# aquatime.net
KiCad netlist of a schematic drawn in EAGLE
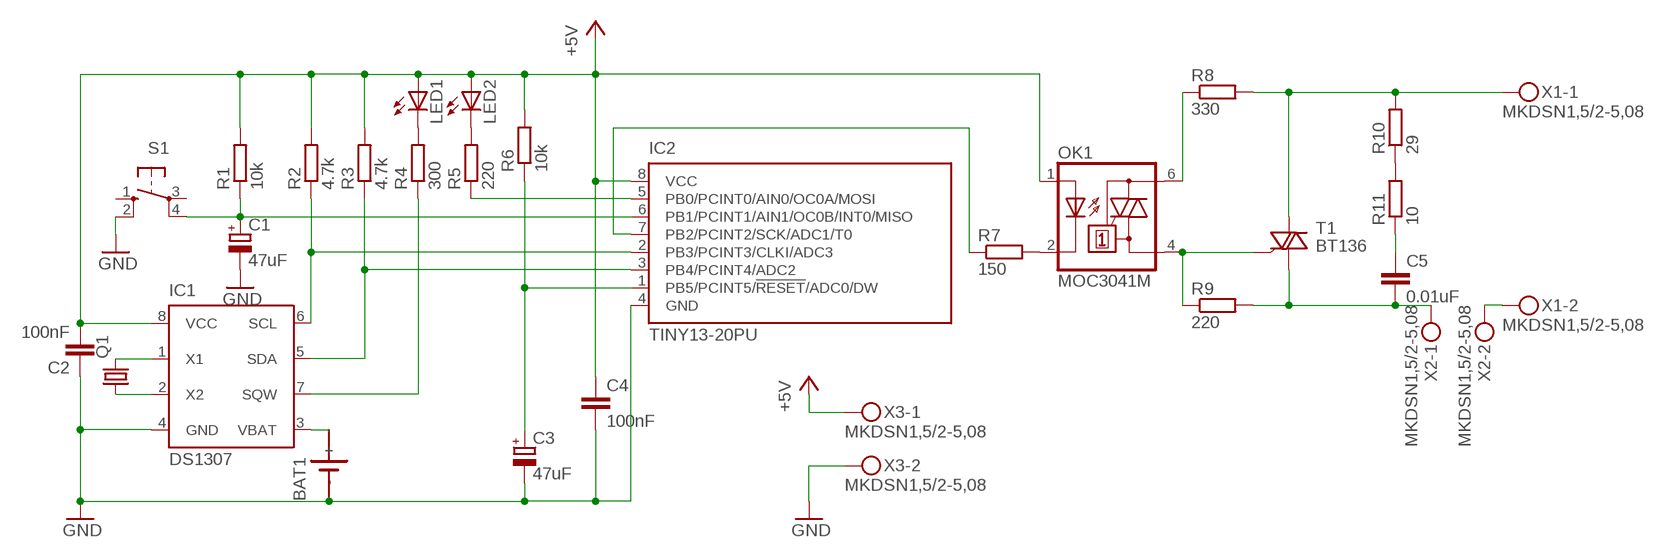
[diagram p0: schematic, sheet 1]

(export (version "E")
  (design (tool "Eeschema 10.0.6"))
  (components
    (comp (ref "BAT1")
      (value "SN2032")
      (footprint "eagle-import:SN2032")
      (libsource (lib "eagle-import") (part "SN2032"))
    )
    (comp (ref "C1")
      (value "47uF")
      (footprint "eagle-import:E2,5-6")
      (libsource (lib "eagle-import") (part "CPOL-EUE2.5-6"))
    )
    (comp (ref "C2")
      (value "100nF")
      (footprint "eagle-import:C102-064X133")
      (libsource (lib "eagle-import") (part "C-EU102-064X133"))
    )
    (comp (ref "C3")
      (value "47uF")
      (footprint "eagle-import:E2,5-6")
      (libsource (lib "eagle-import") (part "CPOL-EUE2.5-6"))
    )
    (comp (ref "C4")
      (value "100nF")
      (footprint "eagle-import:C102-064X133")
      (libsource (lib "eagle-import") (part "C-EU102-064X133"))
    )
    (comp (ref "C5")
      (value "0.01uF")
      (footprint "eagle-import:C102-064X133")
      (libsource (lib "eagle-import") (part "C-EU102-064X133"))
    )
    (comp (ref "IC1")
      (value "DS1307")
      (footprint "eagle-import:DIL08")
      (libsource (lib "eagle-import") (part "DS1307"))
    )
    (comp (ref "IC2")
      (value "TINY13-20PU")
      (footprint "eagle-import:DIL08")
      (fields (field (name "MPN") "ATTINY13-20PU"))
      (libsource (lib "eagle-import") (part "TINY13PU-20"))
    )
    (comp (ref "LED1")
      (value "LED5MM")
      (footprint "eagle-import:LED5MM")
      (libsource (lib "eagle-import") (part "LED5MM"))
    )
    (comp (ref "LED2")
      (value "LED5MM")
      (footprint "eagle-import:LED5MM")
      (libsource (lib "eagle-import") (part "LED5MM"))
    )
    (comp (ref "OK1")
      (value "MOC3041M")
      (footprint "eagle-import:DIL06")
      (fields (field (name "MF") "FAIRCHILD SEMICONDUCTOR"))
      (libsource (lib "eagle-import") (part "MOC3041M"))
    )
    (comp (ref "Q1")
      (value "CRYSTALTC26H")
      (footprint "eagle-import:TC26H")
      (libsource (lib "eagle-import") (part "CRYSTALTC26H"))
    )
    (comp (ref "R1")
      (value "10k")
      (footprint "eagle-import:0207_12")
      (libsource (lib "eagle-import") (part "R-EU_0207/12"))
    )
    (comp (ref "R2")
      (value "4.7k")
      (footprint "eagle-import:0207_10")
      (libsource (lib "eagle-import") (part "R-EU_0207/10"))
    )
    (comp (ref "R3")
      (value "4.7k")
      (footprint "eagle-import:0207_10")
      (libsource (lib "eagle-import") (part "R-EU_0207/10"))
    )
    (comp (ref "R4")
      (value "300")
      (footprint "eagle-import:0207_10")
      (libsource (lib "eagle-import") (part "R-EU_0207/10"))
    )
    (comp (ref "R5")
      (value "220")
      (footprint "eagle-import:0207_10")
      (libsource (lib "eagle-import") (part "R-EU_0207/10"))
    )
    (comp (ref "R6")
      (value "10k")
      (footprint "eagle-import:0207_12")
      (libsource (lib "eagle-import") (part "R-EU_0207/12"))
    )
    (comp (ref "R7")
      (value "150")
      (footprint "eagle-import:0207_10")
      (libsource (lib "eagle-import") (part "R-EU_0207/10"))
    )
    (comp (ref "R8")
      (value "330")
      (footprint "eagle-import:P0817_22")
      (libsource (lib "eagle-import") (part "R-EU_0817/22"))
    )
    (comp (ref "R9")
      (value "220")
      (footprint "eagle-import:0411_15")
      (libsource (lib "eagle-import") (part "R-EU_0411/15"))
    )
    (comp (ref "R10")
      (value "29")
      (footprint "eagle-import:0411_15")
      (libsource (lib "eagle-import") (part "R-EU_0411/15"))
    )
    (comp (ref "R11")
      (value "10")
      (footprint "eagle-import:0411_15")
      (libsource (lib "eagle-import") (part "R-EU_0411/15"))
    )
    (comp (ref "S1")
      (value "10-XX")
      (footprint "eagle-import:B3F-10XX")
      (fields (field (name "MPN") "B3F-1000"))
      (libsource (lib "eagle-import") (part "10-XX"))
    )
    (comp (ref "T1")
      (value "BT136")
      (footprint "eagle-import:TO220AB")
      (libsource (lib "eagle-import") (part "BT136"))
    )
    (comp (ref "X1")
      (value "MKDSN1,5/2-5,08")
      (footprint "eagle-import:MKDSN1,5_2-5,08")
      (libsource (lib "eagle-import") (part "MKDSN1,5/2-5,08"))
    )
    (comp (ref "X2")
      (value "MKDSN1,5/2-5,08")
      (footprint "eagle-import:MKDSN1,5_2-5,08")
      (libsource (lib "eagle-import") (part "MKDSN1,5/2-5,08"))
    )
    (comp (ref "X3")
      (value "MKDSN1,5/2-5,08")
      (footprint "eagle-import:MKDSN1,5_2-5,08")
      (libsource (lib "eagle-import") (part "MKDSN1,5/2-5,08"))
    )
  )
  (nets
    (net (code "1") (name "+5V") (class "Default")
      (node (ref "C2") (pin "2") (pinfunction "2_2") (pintype "passive"))
      (node (ref "C4") (pin "1") (pinfunction "1_1") (pintype "passive"))
      (node (ref "IC1") (pin "8") (pinfunction "VCC_8") (pintype "power_in"))
      (node (ref "IC2") (pin "8") (pinfunction "VCC_8") (pintype "power_in"))
      (node (ref "LED1") (pin "A") (pinfunction "A_A") (pintype "passive"))
      (node (ref "LED2") (pin "A") (pinfunction "A_A") (pintype "passive"))
      (node (ref "OK1") (pin "1") (pinfunction "A_1") (pintype "passive"))
      (node (ref "R1") (pin "2") (pinfunction "2_2") (pintype "passive"))
      (node (ref "R2") (pin "2") (pinfunction "2_2") (pintype "passive"))
      (node (ref "R3") (pin "2") (pinfunction "2_2") (pintype "passive"))
      (node (ref "R6") (pin "2") (pinfunction "2_2") (pintype "passive"))
      (node (ref "X3") (pin "1") (pinfunction "KL_1") (pintype "passive"))
    )
    (net (code "2") (name "GND") (class "Default")
      (node (ref "BAT1") (pin "-") (pinfunction "-_-") (pintype "passive"))
      (node (ref "C1") (pin "-") (pinfunction "-_-") (pintype "passive"))
      (node (ref "C2") (pin "1") (pinfunction "1_1") (pintype "passive"))
      (node (ref "C3") (pin "-") (pinfunction "-_-") (pintype "passive"))
      (node (ref "C4") (pin "2") (pinfunction "2_2") (pintype "passive"))
      (node (ref "IC1") (pin "4") (pinfunction "GND_4") (pintype "power_in"))
      (node (ref "IC2") (pin "4") (pinfunction "GND_4") (pintype "power_in"))
      (node (ref "S1") (pin "2") (pinfunction "S1_2") (pintype "passive"))
      (node (ref "X3") (pin "2") (pinfunction "KL_2") (pintype "passive"))
    )
    (net (code "3") (name "Net-(C5-Pad1)") (class "Default")
      (node (ref "C5") (pin "1") (pinfunction "1_1") (pintype "passive"))
      (node (ref "R11") (pin "1") (pinfunction "1_1") (pintype "passive"))
    )
    (net (code "4") (name "Net-(IC1-SCL)") (class "Default")
      (node (ref "IC1") (pin "6") (pinfunction "SCL_6") (pintype "input"))
      (node (ref "IC2") (pin "2") (pinfunction "PB3/PCINT3/CLKI/ADC3_2") (pintype "bidirectional"))
      (node (ref "R2") (pin "1") (pinfunction "1_1") (pintype "passive"))
    )
    (net (code "5") (name "Net-(IC1-SDA)") (class "Default")
      (node (ref "IC1") (pin "5") (pinfunction "SDA_5") (pintype "bidirectional"))
      (node (ref "IC2") (pin "3") (pinfunction "PB4/PCINT4/ADC2_3") (pintype "bidirectional"))
      (node (ref "R3") (pin "1") (pinfunction "1_1") (pintype "passive"))
    )
    (net (code "6") (name "Net-(IC1-SQW)") (class "Default")
      (node (ref "IC1") (pin "7") (pinfunction "SQW_7") (pintype "open_collector"))
      (node (ref "R4") (pin "1") (pinfunction "1_1") (pintype "passive"))
    )
    (net (code "7") (name "Net-(IC1-VBAT)") (class "Default")
      (node (ref "BAT1") (pin "+") (pinfunction "+_+") (pintype "passive"))
      (node (ref "IC1") (pin "3") (pinfunction "VBAT_3") (pintype "passive"))
    )
    (net (code "8") (name "Net-(IC1-X1)") (class "Default")
      (node (ref "IC1") (pin "1") (pinfunction "X1_1") (pintype "input"))
      (node (ref "Q1") (pin "2") (pinfunction "2_2") (pintype "passive"))
    )
    (net (code "9") (name "Net-(IC1-X2)") (class "Default")
      (node (ref "IC1") (pin "2") (pinfunction "X2_2") (pintype "output"))
      (node (ref "Q1") (pin "1") (pinfunction "1_1") (pintype "passive"))
    )
    (net (code "10") (name "Net-(IC2-PB0{slash}PCINT0{slash}AIN0{slash}OC0A{slash}MOSI)") (class "Default")
      (node (ref "IC2") (pin "5") (pinfunction "PB0/PCINT0/AIN0/OC0A/MOSI_5") (pintype "bidirectional"))
      (node (ref "R5") (pin "1") (pinfunction "1_1") (pintype "passive"))
    )
    (net (code "11") (name "Net-(IC2-PB1{slash}PCINT1{slash}AIN1{slash}OC0B{slash}INT0{slash}MISO)") (class "Default")
      (node (ref "C1") (pin "+") (pinfunction "+_+") (pintype "passive"))
      (node (ref "IC2") (pin "6") (pinfunction "PB1/PCINT1/AIN1/OC0B/INT0/MISO_6") (pintype "bidirectional"))
      (node (ref "R1") (pin "1") (pinfunction "1_1") (pintype "passive"))
      (node (ref "S1") (pin "4") (pinfunction "P1_4") (pintype "passive"))
    )
    (net (code "12") (name "Net-(IC2-PB2{slash}PCINT2{slash}SCK{slash}ADC1{slash}T0)") (class "Default")
      (node (ref "IC2") (pin "7") (pinfunction "PB2/PCINT2/SCK/ADC1/T0_7") (pintype "bidirectional"))
      (node (ref "R7") (pin "1") (pinfunction "1_1") (pintype "passive"))
    )
    (net (code "13") (name "Net-(IC2-PB5{slash}PCINT5{slash}~{RESET}{slash}ADC0{slash}DW)") (class "Default")
      (node (ref "C3") (pin "+") (pinfunction "+_+") (pintype "passive"))
      (node (ref "IC2") (pin "1") (pinfunction "PB5/PCINT5/~{RESET}/ADC0/DW_1") (pintype "bidirectional"))
      (node (ref "R6") (pin "1") (pinfunction "1_1") (pintype "passive"))
    )
    (net (code "14") (name "Net-(LED1-C)") (class "Default")
      (node (ref "LED1") (pin "K") (pinfunction "C_K") (pintype "passive"))
      (node (ref "R4") (pin "2") (pinfunction "2_2") (pintype "passive"))
    )
    (net (code "15") (name "Net-(LED2-C)") (class "Default")
      (node (ref "LED2") (pin "K") (pinfunction "C_K") (pintype "passive"))
      (node (ref "R5") (pin "2") (pinfunction "2_2") (pintype "passive"))
    )
    (net (code "16") (name "Net-(OK1-A1)") (class "Default")
      (node (ref "OK1") (pin "4") (pinfunction "A1_4") (pintype "passive"))
      (node (ref "R9") (pin "1") (pinfunction "1_1") (pintype "passive"))
      (node (ref "T1") (pin "3") (pinfunction "G_3") (pintype "passive"))
    )
    (net (code "17") (name "Net-(OK1-A2)") (class "Default")
      (node (ref "OK1") (pin "6") (pinfunction "A2_6") (pintype "passive"))
      (node (ref "R8") (pin "1") (pinfunction "1_1") (pintype "passive"))
    )
    (net (code "18") (name "Net-(OK1-C)") (class "Default")
      (node (ref "OK1") (pin "2") (pinfunction "C_2") (pintype "passive"))
      (node (ref "R7") (pin "2") (pinfunction "2_2") (pintype "passive"))
    )
    (net (code "19") (name "Net-(R10-Pad1)") (class "Default")
      (node (ref "R10") (pin "1") (pinfunction "1_1") (pintype "passive"))
      (node (ref "R11") (pin "2") (pinfunction "2_2") (pintype "passive"))
    )
    (net (code "20") (name "Net-(T1-A1)") (class "Default")
      (node (ref "C5") (pin "2") (pinfunction "2_2") (pintype "passive"))
      (node (ref "R9") (pin "2") (pinfunction "2_2") (pintype "passive"))
      (node (ref "T1") (pin "1") (pinfunction "A1_1") (pintype "passive"))
      (node (ref "X2") (pin "1") (pinfunction "KL_1") (pintype "passive"))
    )
    (net (code "21") (name "Net-(T1-A2)") (class "Default")
      (node (ref "R10") (pin "2") (pinfunction "2_2") (pintype "passive"))
      (node (ref "R8") (pin "2") (pinfunction "2_2") (pintype "passive"))
      (node (ref "T1") (pin "2") (pinfunction "A2_2") (pintype "passive"))
      (node (ref "X1") (pin "1") (pinfunction "KL_1") (pintype "passive"))
    )
    (net (code "22") (name "Net-(X1B-KL)") (class "Default")
      (node (ref "X1") (pin "2") (pinfunction "KL_2") (pintype "passive"))
      (node (ref "X2") (pin "2") (pinfunction "KL_2") (pintype "passive"))
    )
    (net (code "23") (name "unconnected-(S1-P-Pad3)") (class "Default")
      (node (ref "S1") (pin "3") (pinfunction "P_3") (pintype "passive"))
    )
    (net (code "24") (name "unconnected-(S1-S-Pad1)") (class "Default")
      (node (ref "S1") (pin "1") (pinfunction "S_1") (pintype "passive"))
    )
  )
)
